# ES9023.net
KiCad netlist of a schematic drawn in Altium Designer
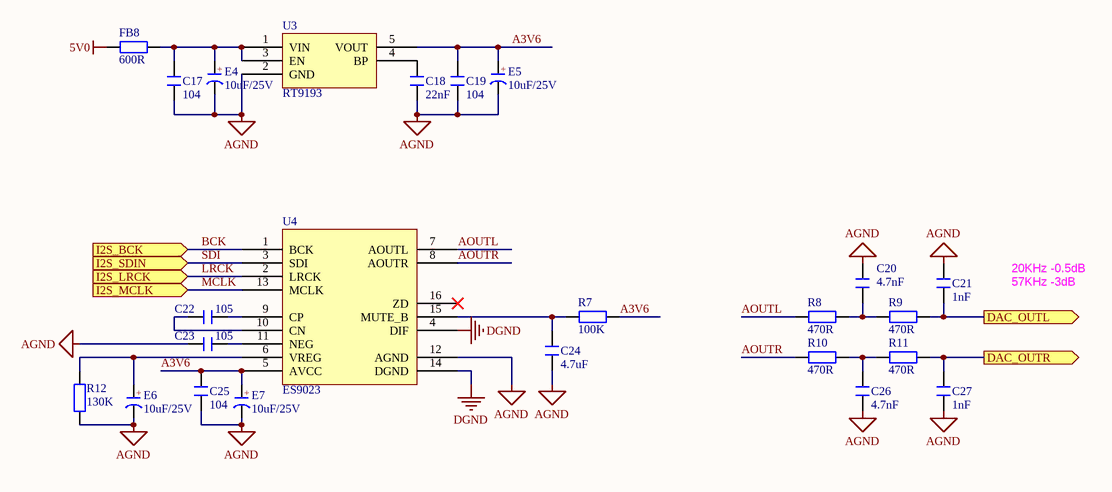
[diagram p0: ES9023.SchDoc]

(export (version "E")
  (design (tool "Eeschema 10.0.6"))
  (components
    (comp (ref "C17")
      (value "104")
      (footprint "C 0603_L")
      (description "贴片电容")
      (libsource (lib "0.1 - 电阻-电容-电感") (part "C"))
    )
    (comp (ref "C18")
      (value "22nF")
      (footprint "C 0603_L")
      (description "贴片电容")
      (libsource (lib "0.1 - 电阻-电容-电感") (part "C"))
    )
    (comp (ref "C19")
      (value "104")
      (footprint "C 0603_L")
      (description "贴片电容")
      (libsource (lib "0.1 - 电阻-电容-电感") (part "C"))
    )
    (comp (ref "C20")
      (value "4.7nF")
      (footprint "C 0603_L")
      (description "贴片电容")
      (libsource (lib "0.1 - 电阻-电容-电感") (part "C"))
    )
    (comp (ref "C21")
      (value "1nF")
      (footprint "C 0603_L")
      (description "贴片电容")
      (libsource (lib "0.1 - 电阻-电容-电感") (part "C"))
    )
    (comp (ref "C22")
      (value "105")
      (footprint "C 0603_L")
      (description "贴片电容")
      (libsource (lib "0.1 - 电阻-电容-电感") (part "C"))
    )
    (comp (ref "C23")
      (value "105")
      (footprint "C 0603_L")
      (description "贴片电容")
      (libsource (lib "0.1 - 电阻-电容-电感") (part "C"))
    )
    (comp (ref "C24")
      (value "4.7uF")
      (footprint "C 0603_L")
      (description "贴片电容")
      (libsource (lib "0.1 - 电阻-电容-电感") (part "C"))
    )
    (comp (ref "C25")
      (value "104")
      (footprint "C 0603_L")
      (description "贴片电容")
      (libsource (lib "0.1 - 电阻-电容-电感") (part "C"))
    )
    (comp (ref "C26")
      (value "4.7nF")
      (footprint "C 0603_L")
      (description "贴片电容")
      (libsource (lib "0.1 - 电阻-电容-电感") (part "C"))
    )
    (comp (ref "C27")
      (value "1nF")
      (footprint "C 0603_L")
      (description "贴片电容")
      (libsource (lib "0.1 - 电阻-电容-电感") (part "C"))
    )
    (comp (ref "E4")
      (value "10uF/25V")
      (footprint "CD A(3216)")
      (description "贴片钽电容")
      (libsource (lib "0.1 - 电阻-电容-电感") (part "CT"))
    )
    (comp (ref "E5")
      (value "10uF/25V")
      (footprint "CD A(3216)")
      (description "贴片钽电容")
      (libsource (lib "0.1 - 电阻-电容-电感") (part "CT"))
    )
    (comp (ref "E6")
      (value "10uF/25V")
      (footprint "CD A(3216)")
      (description "贴片钽电容")
      (libsource (lib "0.1 - 电阻-电容-电感") (part "CT"))
    )
    (comp (ref "E7")
      (value "10uF/25V")
      (footprint "CD A(3216)")
      (description "贴片钽电容")
      (libsource (lib "0.1 - 电阻-电容-电感") (part "CT"))
    )
    (comp (ref "FB8")
      (value "600R")
      (footprint "R 0805_L")
      (description "贴片电阻")
      (libsource (lib "0.1 - 电阻-电容-电感") (part "R"))
    )
    (comp (ref "R7")
      (value "100K")
      (footprint "R 0603_L")
      (description "贴片电阻")
      (libsource (lib "0.1 - 电阻-电容-电感") (part "R"))
    )
    (comp (ref "R8")
      (value "470R")
      (footprint "R 0603_L")
      (description "贴片电阻")
      (libsource (lib "0.1 - 电阻-电容-电感") (part "R"))
    )
    (comp (ref "R9")
      (value "470R")
      (footprint "R 0603_L")
      (description "贴片电阻")
      (libsource (lib "0.1 - 电阻-电容-电感") (part "R"))
    )
    (comp (ref "R10")
      (value "470R")
      (footprint "R 0603_L")
      (description "贴片电阻")
      (libsource (lib "0.1 - 电阻-电容-电感") (part "R"))
    )
    (comp (ref "R11")
      (value "470R")
      (footprint "R 0603_L")
      (description "贴片电阻")
      (libsource (lib "0.1 - 电阻-电容-电感") (part "R"))
    )
    (comp (ref "R12")
      (value "130K")
      (footprint "R 0603_L")
      (description "贴片电阻")
      (libsource (lib "0.1 - 电阻-电容-电感") (part "R"))
    )
    (comp (ref "U3")
      (value "RT9193")
      (footprint "SOT23-5N")
      (description "高PSRR低噪声高速稳压")
      (libsource (lib "1.1 - 电源类芯片") (part "RT9193"))
    )
    (comp (ref "U4")
      (value "ES9023")
      (footprint "SOP16_N")
      (description "24bit DAC 2Vrms")
      (libsource (lib "音频芯片") (part "ES9023"))
    )
  )
  (nets
    (net (code "1") (name "/A3V6") (class "Default")
      (node (ref "C19") (pin "2") (pinfunction "2_2") (pintype "passive"))
      (node (ref "C25") (pin "2") (pinfunction "2_2") (pintype "passive"))
      (node (ref "E5") (pin "1") (pinfunction "A_1") (pintype "passive"))
      (node (ref "E7") (pin "1") (pinfunction "A_1") (pintype "passive"))
      (node (ref "R7") (pin "1") (pinfunction "1_1") (pintype "passive"))
      (node (ref "U3") (pin "5") (pinfunction "VOUT_5") (pintype "passive"))
      (node (ref "U4") (pin "5") (pinfunction "AVCC_5") (pintype "passive"))
    )
    (net (code "2") (name "/AOUTL") (class "Default")
      (node (ref "R8") (pin "2") (pinfunction "2_2") (pintype "passive"))
      (node (ref "U4") (pin "7") (pinfunction "AOUTL_7") (pintype "passive"))
    )
    (net (code "3") (name "/AOUTR") (class "Default")
      (node (ref "R10") (pin "2") (pinfunction "2_2") (pintype "passive"))
      (node (ref "U4") (pin "8") (pinfunction "AOUTR_8") (pintype "passive"))
    )
    (net (code "4") (name "/BCK") (class "Default")
      (node (ref "U4") (pin "1") (pinfunction "BCK_1") (pintype "passive"))
    )
    (net (code "5") (name "/DAC_OUTL") (class "Default")
      (node (ref "C21") (pin "1") (pinfunction "1_1") (pintype "passive"))
      (node (ref "R9") (pin "1") (pinfunction "1_1") (pintype "passive"))
    )
    (net (code "6") (name "/DAC_OUTR") (class "Default")
      (node (ref "C27") (pin "2") (pinfunction "2_2") (pintype "passive"))
      (node (ref "R11") (pin "1") (pinfunction "1_1") (pintype "passive"))
    )
    (net (code "7") (name "/LRCK") (class "Default")
      (node (ref "U4") (pin "2") (pinfunction "LRCK_2") (pintype "passive"))
    )
    (net (code "8") (name "/MCLK") (class "Default")
      (node (ref "U4") (pin "13") (pinfunction "MCLK_13") (pintype "passive"))
    )
    (net (code "9") (name "/SDI") (class "Default")
      (node (ref "U4") (pin "3") (pinfunction "SDI_3") (pintype "passive"))
    )
    (net (code "10") (name "5V0") (class "Default")
      (node (ref "FB8") (pin "1") (pinfunction "1_1") (pintype "passive"))
    )
    (net (code "11") (name "AGND") (class "Default")
      (node (ref "C17") (pin "1") (pinfunction "1_1") (pintype "passive"))
      (node (ref "C18") (pin "1") (pinfunction "1_1") (pintype "passive"))
      (node (ref "C19") (pin "1") (pinfunction "1_1") (pintype "passive"))
      (node (ref "C20") (pin "2") (pinfunction "2_2") (pintype "passive"))
      (node (ref "C21") (pin "2") (pinfunction "2_2") (pintype "passive"))
      (node (ref "C23") (pin "2") (pinfunction "2_2") (pintype "passive"))
      (node (ref "C24") (pin "2") (pinfunction "2_2") (pintype "passive"))
      (node (ref "C25") (pin "1") (pinfunction "1_1") (pintype "passive"))
      (node (ref "C26") (pin "1") (pinfunction "1_1") (pintype "passive"))
      (node (ref "C27") (pin "1") (pinfunction "1_1") (pintype "passive"))
      (node (ref "E4") (pin "2") (pinfunction "K_2") (pintype "passive"))
      (node (ref "E5") (pin "2") (pinfunction "K_2") (pintype "passive"))
      (node (ref "E6") (pin "2") (pinfunction "K_2") (pintype "passive"))
      (node (ref "E7") (pin "2") (pinfunction "K_2") (pintype "passive"))
      (node (ref "R12") (pin "1") (pinfunction "1_1") (pintype "passive"))
      (node (ref "U3") (pin "2") (pinfunction "GND_2") (pintype "passive"))
      (node (ref "U4") (pin "12") (pinfunction "AGND_12") (pintype "passive"))
    )
    (net (code "12") (name "DGND") (class "Default")
      (node (ref "U4") (pin "14") (pinfunction "DGND_14") (pintype "passive"))
      (node (ref "U4") (pin "4") (pinfunction "DIF_4") (pintype "passive"))
    )
    (net (code "13") (name "Net-(C20-Pad1)") (class "Default")
      (node (ref "C20") (pin "1") (pinfunction "1_1") (pintype "passive"))
      (node (ref "R8") (pin "1") (pinfunction "1_1") (pintype "passive"))
      (node (ref "R9") (pin "2") (pinfunction "2_2") (pintype "passive"))
    )
    (net (code "14") (name "Net-(C26-Pad2)") (class "Default")
      (node (ref "C26") (pin "2") (pinfunction "2_2") (pintype "passive"))
      (node (ref "R10") (pin "1") (pinfunction "1_1") (pintype "passive"))
      (node (ref "R11") (pin "2") (pinfunction "2_2") (pintype "passive"))
    )
    (net (code "15") (name "Net-(E4-A)") (class "Default")
      (node (ref "C17") (pin "2") (pinfunction "2_2") (pintype "passive"))
      (node (ref "E4") (pin "1") (pinfunction "A_1") (pintype "passive"))
      (node (ref "FB8") (pin "2") (pinfunction "2_2") (pintype "passive"))
      (node (ref "U3") (pin "1") (pinfunction "VIN_1") (pintype "passive"))
      (node (ref "U3") (pin "3") (pinfunction "EN_3") (pintype "passive"))
    )
    (net (code "16") (name "Net-(E6-A)") (class "Default")
      (node (ref "E6") (pin "1") (pinfunction "A_1") (pintype "passive"))
      (node (ref "R12") (pin "2") (pinfunction "2_2") (pintype "passive"))
      (node (ref "U4") (pin "6") (pinfunction "VREG_6") (pintype "passive"))
    )
    (net (code "17") (name "Net-(U3-BP)") (class "Default")
      (node (ref "C18") (pin "2") (pinfunction "2_2") (pintype "passive"))
      (node (ref "U3") (pin "4") (pinfunction "BP_4") (pintype "passive"))
    )
    (net (code "18") (name "Net-(U4-CN)") (class "Default")
      (node (ref "C22") (pin "2") (pinfunction "2_2") (pintype "passive"))
      (node (ref "U4") (pin "10") (pinfunction "CN_10") (pintype "passive"))
    )
    (net (code "19") (name "Net-(U4-CP)") (class "Default")
      (node (ref "C22") (pin "1") (pinfunction "1_1") (pintype "passive"))
      (node (ref "U4") (pin "9") (pinfunction "CP_9") (pintype "passive"))
    )
    (net (code "20") (name "Net-(U4-MUTE_B)") (class "Default")
      (node (ref "C24") (pin "1") (pinfunction "1_1") (pintype "passive"))
      (node (ref "R7") (pin "2") (pinfunction "2_2") (pintype "passive"))
      (node (ref "U4") (pin "15") (pinfunction "MUTE_B_15") (pintype "passive"))
    )
    (net (code "21") (name "Net-(U4-NEG)") (class "Default")
      (node (ref "C23") (pin "1") (pinfunction "1_1") (pintype "passive"))
      (node (ref "U4") (pin "11") (pinfunction "NEG_11") (pintype "passive"))
    )
    (net (code "22") (name "unconnected-(U4-ZD-Pad16)") (class "Default")
      (node (ref "U4") (pin "16") (pinfunction "ZD_16") (pintype "passive+no_connect"))
    )
  )
)
